# EQTest.net
KiCad netlist of a schematic drawn in EAGLE
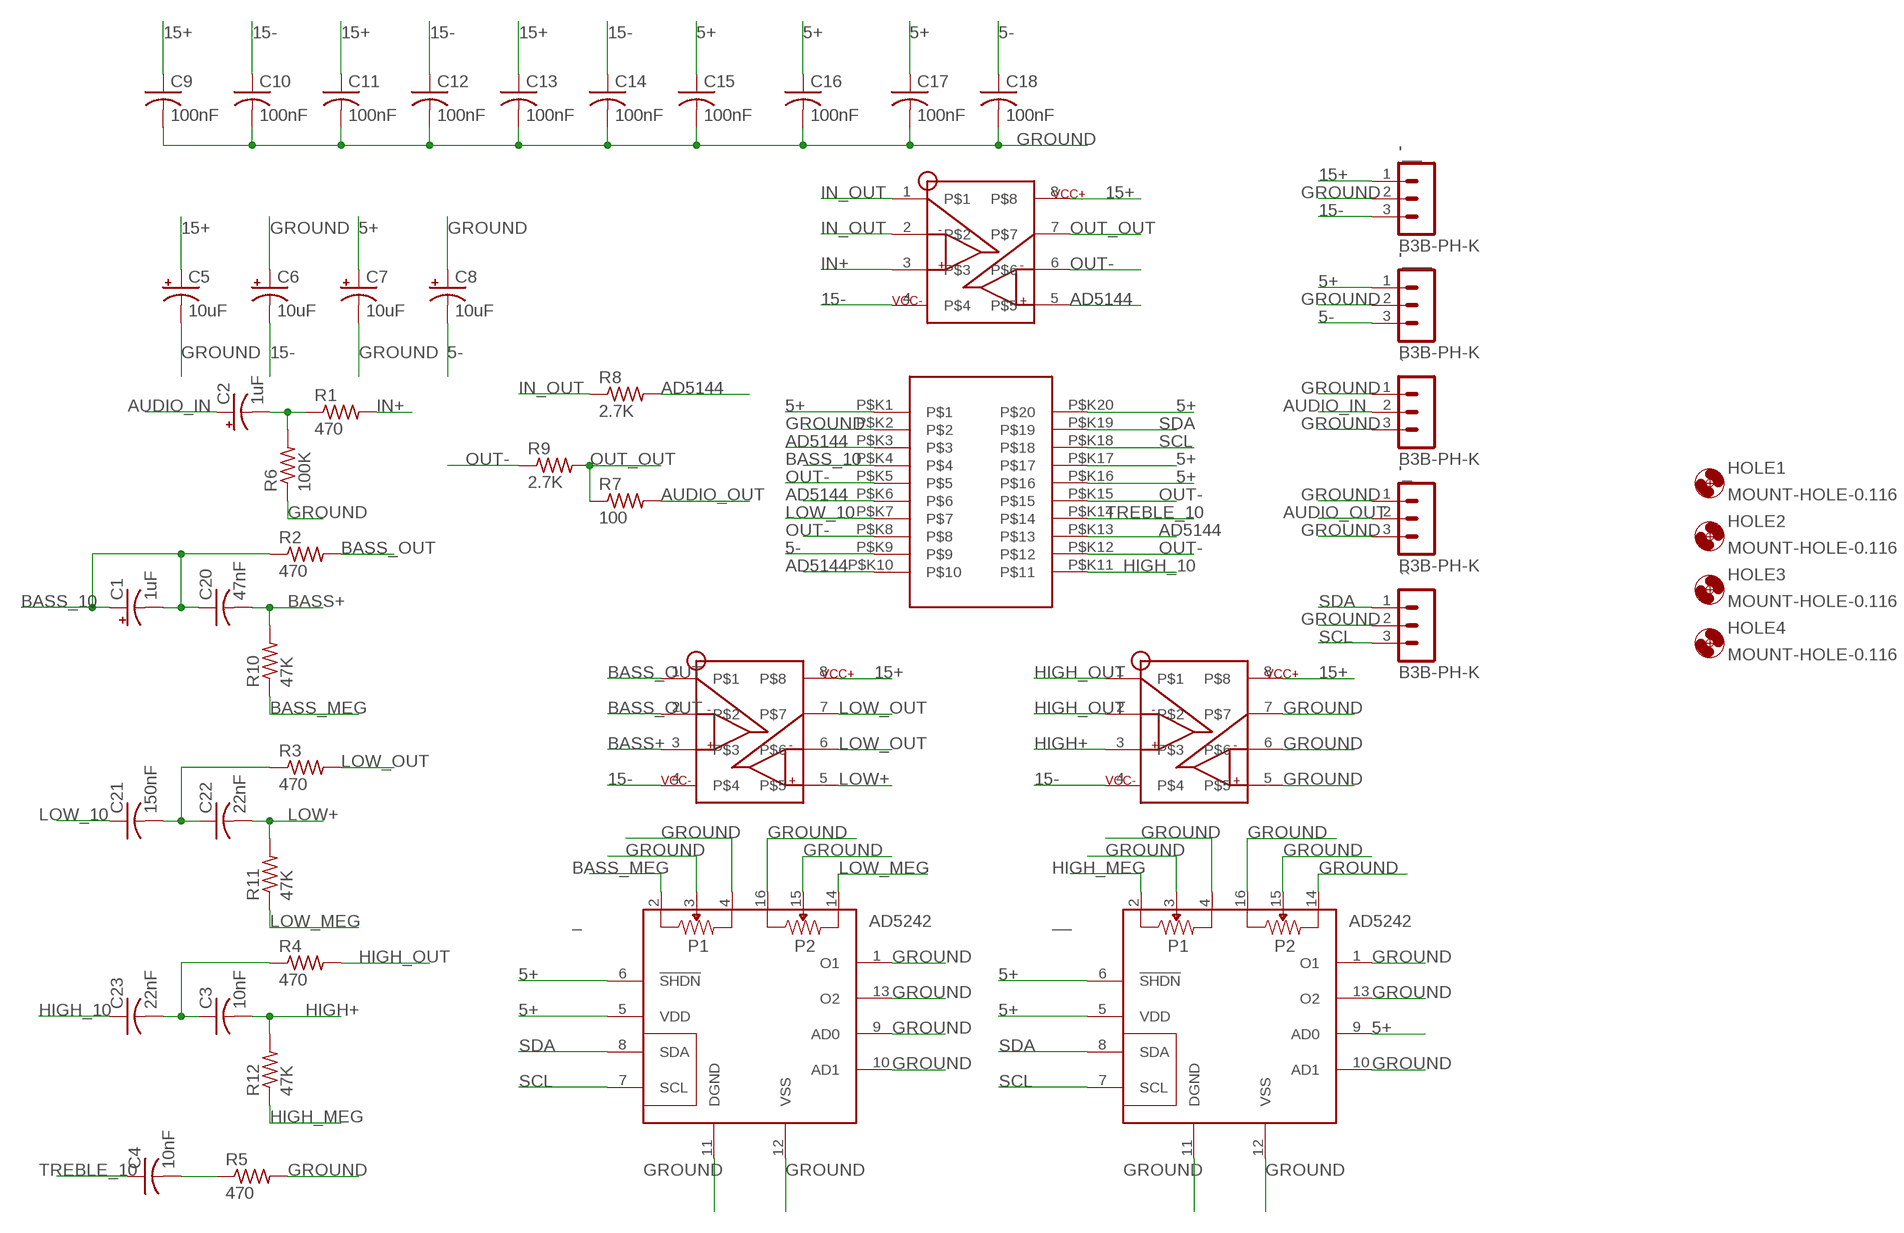
[diagram p0: schematic, sheet 1]

(export (version "E")
  (design (tool "Eeschema 10.0.6"))
  (components
    (comp (ref "'")
      (value "NE5532")
      (footprint "eagle-import:SO08")
      (libsource (lib "eagle-import") (part "NE5532"))
    )
    (comp (ref "''")
      (value "NE5532")
      (footprint "eagle-import:SO08")
      (libsource (lib "eagle-import") (part "NE5532"))
    )
    (comp (ref "'''")
      (value "NE5532")
      (footprint "eagle-import:SO08")
      (libsource (lib "eagle-import") (part "NE5532"))
    )
    (comp (ref "'_")
      (value "B3B-PH-K")
      (footprint "eagle-import:B3B-PH-K")
      (libsource (lib "eagle-import") (part "B3B-PH-K"))
    )
    (comp (ref "'__")
      (value "B3B-PH-K")
      (footprint "eagle-import:B3B-PH-K")
      (libsource (lib "eagle-import") (part "B3B-PH-K"))
    )
    (comp (ref "'___")
      (value "B3B-PH-K")
      (footprint "eagle-import:B3B-PH-K")
      (libsource (lib "eagle-import") (part "B3B-PH-K"))
    )
    (comp (ref "10K")
      (value "TSSOP20")
      (footprint "eagle-import:TSSOP20")
      (libsource (lib "eagle-import") (part "TSSOP20"))
    )
    (comp (ref "C1")
      (value "1uF")
      (footprint "eagle-import:E2-5")
      (libsource (lib "eagle-import") (part "CPOL-USE2-5"))
    )
    (comp (ref "C2")
      (value "1uF")
      (footprint "eagle-import:E2-5")
      (libsource (lib "eagle-import") (part "CPOL-USE2-5"))
    )
    (comp (ref "C3")
      (value "10nF")
      (footprint "eagle-import:C1206K")
      (libsource (lib "eagle-import") (part "C-USC1206K"))
    )
    (comp (ref "C4")
      (value "10nF")
      (footprint "eagle-import:C1206K")
      (libsource (lib "eagle-import") (part "C-USC1206K"))
    )
    (comp (ref "C5")
      (value "10uF")
      (footprint "eagle-import:E3,5-8")
      (libsource (lib "eagle-import") (part "CPOL-USE3.5-8"))
    )
    (comp (ref "C6")
      (value "10uF")
      (footprint "eagle-import:E3,5-8")
      (libsource (lib "eagle-import") (part "CPOL-USE3.5-8"))
    )
    (comp (ref "C7")
      (value "10uF")
      (footprint "eagle-import:E3,5-8")
      (libsource (lib "eagle-import") (part "CPOL-USE3.5-8"))
    )
    (comp (ref "C8")
      (value "10uF")
      (footprint "eagle-import:E3,5-8")
      (libsource (lib "eagle-import") (part "CPOL-USE3.5-8"))
    )
    (comp (ref "C9")
      (value "100nF")
      (footprint "eagle-import:C1206K")
      (libsource (lib "eagle-import") (part "C-USC1206K"))
    )
    (comp (ref "C10")
      (value "100nF")
      (footprint "eagle-import:C1206K")
      (libsource (lib "eagle-import") (part "C-USC1206K"))
    )
    (comp (ref "C11")
      (value "100nF")
      (footprint "eagle-import:C1206K")
      (libsource (lib "eagle-import") (part "C-USC1206K"))
    )
    (comp (ref "C12")
      (value "100nF")
      (footprint "eagle-import:C1206K")
      (libsource (lib "eagle-import") (part "C-USC1206K"))
    )
    (comp (ref "C13")
      (value "100nF")
      (footprint "eagle-import:C1206K")
      (libsource (lib "eagle-import") (part "C-USC1206K"))
    )
    (comp (ref "C14")
      (value "100nF")
      (footprint "eagle-import:C1206K")
      (libsource (lib "eagle-import") (part "C-USC1206K"))
    )
    (comp (ref "C15")
      (value "100nF")
      (footprint "eagle-import:C1206K")
      (libsource (lib "eagle-import") (part "C-USC1206K"))
    )
    (comp (ref "C16")
      (value "100nF")
      (footprint "eagle-import:C1206K")
      (libsource (lib "eagle-import") (part "C-USC1206K"))
    )
    (comp (ref "C17")
      (value "100nF")
      (footprint "eagle-import:C1206K")
      (libsource (lib "eagle-import") (part "C-USC1206K"))
    )
    (comp (ref "C18")
      (value "100nF")
      (footprint "eagle-import:C1206K")
      (libsource (lib "eagle-import") (part "C-USC1206K"))
    )
    (comp (ref "C20")
      (value "47nF")
      (footprint "eagle-import:C1206K")
      (libsource (lib "eagle-import") (part "C-USC1206K"))
    )
    (comp (ref "C21")
      (value "150nF")
      (footprint "eagle-import:C1206K")
      (libsource (lib "eagle-import") (part "C-USC1206K"))
    )
    (comp (ref "C22")
      (value "22nF")
      (footprint "eagle-import:C1206K")
      (libsource (lib "eagle-import") (part "C-USC1206K"))
    )
    (comp (ref "C23")
      (value "22nF")
      (footprint "eagle-import:C1206K")
      (libsource (lib "eagle-import") (part "C-USC1206K"))
    )
    (comp (ref "HOLE1")
      (value "MOUNT-HOLE-0.116")
      (footprint "eagle-import:116")
      (libsource (lib "eagle-import") (part "MOUNT-HOLE-0.116"))
    )
    (comp (ref "HOLE2")
      (value "MOUNT-HOLE-0.116")
      (footprint "eagle-import:116")
      (libsource (lib "eagle-import") (part "MOUNT-HOLE-0.116"))
    )
    (comp (ref "HOLE3")
      (value "MOUNT-HOLE-0.116")
      (footprint "eagle-import:116")
      (libsource (lib "eagle-import") (part "MOUNT-HOLE-0.116"))
    )
    (comp (ref "HOLE4")
      (value "MOUNT-HOLE-0.116")
      (footprint "eagle-import:116")
      (libsource (lib "eagle-import") (part "MOUNT-HOLE-0.116"))
    )
    (comp (ref "R1")
      (value "470")
      (footprint "eagle-import:R1206")
      (libsource (lib "eagle-import") (part "R-US_R1206"))
    )
    (comp (ref "R2")
      (value "470")
      (footprint "eagle-import:R1206")
      (libsource (lib "eagle-import") (part "R-US_R1206"))
    )
    (comp (ref "R3")
      (value "470")
      (footprint "eagle-import:R1206")
      (libsource (lib "eagle-import") (part "R-US_R1206"))
    )
    (comp (ref "R4")
      (value "470")
      (footprint "eagle-import:R1206")
      (libsource (lib "eagle-import") (part "R-US_R1206"))
    )
    (comp (ref "R5")
      (value "470")
      (footprint "eagle-import:R1206")
      (libsource (lib "eagle-import") (part "R-US_R1206"))
    )
    (comp (ref "R6")
      (value "100K")
      (footprint "eagle-import:R1206")
      (libsource (lib "eagle-import") (part "R-US_R1206"))
    )
    (comp (ref "R7")
      (value "100")
      (footprint "eagle-import:R1206")
      (libsource (lib "eagle-import") (part "R-US_R1206"))
    )
    (comp (ref "R8")
      (value "2.7K")
      (footprint "eagle-import:R1206")
      (libsource (lib "eagle-import") (part "R-US_R1206"))
    )
    (comp (ref "R9")
      (value "2.7K")
      (footprint "eagle-import:R1206")
      (libsource (lib "eagle-import") (part "R-US_R1206"))
    )
    (comp (ref "R10")
      (value "47K")
      (footprint "eagle-import:R1206")
      (libsource (lib "eagle-import") (part "R-US_R1206"))
    )
    (comp (ref "R11")
      (value "47K")
      (footprint "eagle-import:R1206")
      (libsource (lib "eagle-import") (part "R-US_R1206"))
    )
    (comp (ref "R12")
      (value "47K")
      (footprint "eagle-import:R1206")
      (libsource (lib "eagle-import") (part "R-US_R1206"))
    )
    (comp (ref "_")
      (value "AD5242")
      (footprint "eagle-import:TSSOP16")
      (libsource (lib "eagle-import") (part "AD5242"))
    )
    (comp (ref "__")
      (value "AD5242")
      (footprint "eagle-import:TSSOP16")
      (libsource (lib "eagle-import") (part "AD5242"))
    )
    (comp (ref "`")
      (value "B3B-PH-K")
      (footprint "eagle-import:B3B-PH-K")
      (libsource (lib "eagle-import") (part "B3B-PH-K"))
    )
    (comp (ref "``")
      (value "B3B-PH-K")
      (footprint "eagle-import:B3B-PH-K")
      (libsource (lib "eagle-import") (part "B3B-PH-K"))
    )
  )
  (nets
    (net (code "1") (name "/5+") (class "Default")
      (node (ref "'___") (pin "1") (pinfunction "1_1") (pintype "passive"))
      (node (ref "10K") (pin "P$K1") (pinfunction "P$1_P$K1") (pintype "bidirectional"))
      (node (ref "10K") (pin "P$K16") (pinfunction "P$16_P$K16") (pintype "bidirectional"))
      (node (ref "10K") (pin "P$K17") (pinfunction "P$17_P$K17") (pintype "bidirectional"))
      (node (ref "10K") (pin "P$K20") (pinfunction "P$20_P$K20") (pintype "bidirectional"))
      (node (ref "C15") (pin "1") (pinfunction "1_1") (pintype "passive"))
      (node (ref "C16") (pin "1") (pinfunction "1_1") (pintype "passive"))
      (node (ref "C17") (pin "1") (pinfunction "1_1") (pintype "passive"))
      (node (ref "C7") (pin "+") (pinfunction "+_+") (pintype "passive"))
      (node (ref "_") (pin "5") (pinfunction "VDD_5") (pintype "bidirectional"))
      (node (ref "_") (pin "6") (pinfunction "~{SHDN}_6") (pintype "bidirectional"))
      (node (ref "__") (pin "5") (pinfunction "VDD_5") (pintype "bidirectional"))
      (node (ref "__") (pin "6") (pinfunction "~{SHDN}_6") (pintype "bidirectional"))
      (node (ref "__") (pin "9") (pinfunction "AD0_9") (pintype "bidirectional"))
    )
    (net (code "2") (name "/5-") (class "Default")
      (node (ref "'___") (pin "3") (pinfunction "3_3") (pintype "passive"))
      (node (ref "10K") (pin "P$K9") (pinfunction "P$9_P$K9") (pintype "bidirectional"))
      (node (ref "C18") (pin "1") (pinfunction "1_1") (pintype "passive"))
      (node (ref "C8") (pin "-") (pinfunction "-_-") (pintype "passive"))
    )
    (net (code "3") (name "/15+") (class "Default")
      (node (ref "'") (pin "8") (pinfunction "P$8_8") (pintype "bidirectional"))
      (node (ref "''") (pin "8") (pinfunction "P$8_8") (pintype "bidirectional"))
      (node (ref "'''") (pin "8") (pinfunction "P$8_8") (pintype "bidirectional"))
      (node (ref "'__") (pin "1") (pinfunction "1_1") (pintype "passive"))
      (node (ref "C11") (pin "1") (pinfunction "1_1") (pintype "passive"))
      (node (ref "C13") (pin "1") (pinfunction "1_1") (pintype "passive"))
      (node (ref "C5") (pin "+") (pinfunction "+_+") (pintype "passive"))
      (node (ref "C9") (pin "1") (pinfunction "1_1") (pintype "passive"))
    )
    (net (code "4") (name "/15-") (class "Default")
      (node (ref "'") (pin "4") (pinfunction "P$4_4") (pintype "bidirectional"))
      (node (ref "''") (pin "4") (pinfunction "P$4_4") (pintype "bidirectional"))
      (node (ref "'''") (pin "4") (pinfunction "P$4_4") (pintype "bidirectional"))
      (node (ref "'__") (pin "3") (pinfunction "3_3") (pintype "passive"))
      (node (ref "C10") (pin "1") (pinfunction "1_1") (pintype "passive"))
      (node (ref "C12") (pin "1") (pinfunction "1_1") (pintype "passive"))
      (node (ref "C14") (pin "1") (pinfunction "1_1") (pintype "passive"))
      (node (ref "C6") (pin "-") (pinfunction "-_-") (pintype "passive"))
    )
    (net (code "5") (name "/AD5144") (class "Default")
      (node (ref "'") (pin "5") (pinfunction "P$5_5") (pintype "bidirectional"))
      (node (ref "10K") (pin "P$K10") (pinfunction "P$10_P$K10") (pintype "bidirectional"))
      (node (ref "10K") (pin "P$K13") (pinfunction "P$13_P$K13") (pintype "bidirectional"))
      (node (ref "10K") (pin "P$K3") (pinfunction "P$3_P$K3") (pintype "bidirectional"))
      (node (ref "10K") (pin "P$K6") (pinfunction "P$6_P$K6") (pintype "bidirectional"))
      (node (ref "R8") (pin "2") (pinfunction "2_2") (pintype "passive"))
    )
    (net (code "6") (name "/AUDIO_IN") (class "Default")
      (node (ref "C2") (pin "+") (pinfunction "+_+") (pintype "passive"))
      (node (ref "`") (pin "2") (pinfunction "2_2") (pintype "passive"))
    )
    (net (code "7") (name "/AUDIO_OUT") (class "Default")
      (node (ref "'_") (pin "2") (pinfunction "2_2") (pintype "passive"))
      (node (ref "R7") (pin "2") (pinfunction "2_2") (pintype "passive"))
    )
    (net (code "8") (name "/BASS+") (class "Default")
      (node (ref "''") (pin "3") (pinfunction "P$3_3") (pintype "bidirectional"))
      (node (ref "C20") (pin "2") (pinfunction "2_2") (pintype "passive"))
      (node (ref "R10") (pin "2") (pinfunction "2_2") (pintype "passive"))
    )
    (net (code "9") (name "/BASS_10") (class "Default")
      (node (ref "10K") (pin "P$K4") (pinfunction "P$4_P$K4") (pintype "bidirectional"))
      (node (ref "C1") (pin "+") (pinfunction "+_+") (pintype "passive"))
      (node (ref "C1") (pin "-") (pinfunction "-_-") (pintype "passive"))
      (node (ref "C20") (pin "1") (pinfunction "1_1") (pintype "passive"))
      (node (ref "R2") (pin "1") (pinfunction "1_1") (pintype "passive"))
    )
    (net (code "10") (name "/BASS_MEG") (class "Default")
      (node (ref "R10") (pin "1") (pinfunction "1_1") (pintype "passive"))
      (node (ref "_") (pin "2") (pinfunction "A1_2") (pintype "bidirectional"))
    )
    (net (code "11") (name "/BASS_OUT") (class "Default")
      (node (ref "''") (pin "1") (pinfunction "P$1_1") (pintype "bidirectional"))
      (node (ref "''") (pin "2") (pinfunction "P$2_2") (pintype "bidirectional"))
      (node (ref "R2") (pin "2") (pinfunction "2_2") (pintype "passive"))
    )
    (net (code "12") (name "/GROUND") (class "Default")
      (node (ref "'''") (pin "5") (pinfunction "P$5_5") (pintype "bidirectional"))
      (node (ref "'''") (pin "6") (pinfunction "P$6_6") (pintype "bidirectional"))
      (node (ref "'''") (pin "7") (pinfunction "P$7_7") (pintype "bidirectional"))
      (node (ref "'_") (pin "1") (pinfunction "1_1") (pintype "passive"))
      (node (ref "'_") (pin "3") (pinfunction "3_3") (pintype "passive"))
      (node (ref "'__") (pin "2") (pinfunction "2_2") (pintype "passive"))
      (node (ref "'___") (pin "2") (pinfunction "2_2") (pintype "passive"))
      (node (ref "10K") (pin "P$K2") (pinfunction "P$2_P$K2") (pintype "bidirectional"))
      (node (ref "C10") (pin "2") (pinfunction "2_2") (pintype "passive"))
      (node (ref "C11") (pin "2") (pinfunction "2_2") (pintype "passive"))
      (node (ref "C12") (pin "2") (pinfunction "2_2") (pintype "passive"))
      (node (ref "C13") (pin "2") (pinfunction "2_2") (pintype "passive"))
      (node (ref "C14") (pin "2") (pinfunction "2_2") (pintype "passive"))
      (node (ref "C15") (pin "2") (pinfunction "2_2") (pintype "passive"))
      (node (ref "C16") (pin "2") (pinfunction "2_2") (pintype "passive"))
      (node (ref "C17") (pin "2") (pinfunction "2_2") (pintype "passive"))
      (node (ref "C18") (pin "2") (pinfunction "2_2") (pintype "passive"))
      (node (ref "C5") (pin "-") (pinfunction "-_-") (pintype "passive"))
      (node (ref "C6") (pin "+") (pinfunction "+_+") (pintype "passive"))
      (node (ref "C7") (pin "-") (pinfunction "-_-") (pintype "passive"))
      (node (ref "C8") (pin "+") (pinfunction "+_+") (pintype "passive"))
      (node (ref "C9") (pin "2") (pinfunction "2_2") (pintype "passive"))
      (node (ref "R5") (pin "2") (pinfunction "2_2") (pintype "passive"))
      (node (ref "R6") (pin "1") (pinfunction "1_1") (pintype "passive"))
      (node (ref "_") (pin "1") (pinfunction "O1_1") (pintype "bidirectional"))
      (node (ref "_") (pin "10") (pinfunction "AD1_10") (pintype "bidirectional"))
      (node (ref "_") (pin "11") (pinfunction "DGND_11") (pintype "bidirectional"))
      (node (ref "_") (pin "12") (pinfunction "VSS_12") (pintype "bidirectional"))
      (node (ref "_") (pin "13") (pinfunction "O2_13") (pintype "bidirectional"))
      (node (ref "_") (pin "15") (pinfunction "W2_15") (pintype "bidirectional"))
      (node (ref "_") (pin "16") (pinfunction "A2_16") (pintype "bidirectional"))
      (node (ref "_") (pin "3") (pinfunction "W1_3") (pintype "bidirectional"))
      (node (ref "_") (pin "4") (pinfunction "B1_4") (pintype "bidirectional"))
      (node (ref "_") (pin "9") (pinfunction "AD0_9") (pintype "bidirectional"))
      (node (ref "__") (pin "1") (pinfunction "O1_1") (pintype "bidirectional"))
      (node (ref "__") (pin "10") (pinfunction "AD1_10") (pintype "bidirectional"))
      (node (ref "__") (pin "11") (pinfunction "DGND_11") (pintype "bidirectional"))
      (node (ref "__") (pin "12") (pinfunction "VSS_12") (pintype "bidirectional"))
      (node (ref "__") (pin "13") (pinfunction "O2_13") (pintype "bidirectional"))
      (node (ref "__") (pin "14") (pinfunction "B2_14") (pintype "bidirectional"))
      (node (ref "__") (pin "15") (pinfunction "W2_15") (pintype "bidirectional"))
      (node (ref "__") (pin "16") (pinfunction "A2_16") (pintype "bidirectional"))
      (node (ref "__") (pin "3") (pinfunction "W1_3") (pintype "bidirectional"))
      (node (ref "__") (pin "4") (pinfunction "B1_4") (pintype "bidirectional"))
      (node (ref "`") (pin "1") (pinfunction "1_1") (pintype "passive"))
      (node (ref "`") (pin "3") (pinfunction "3_3") (pintype "passive"))
      (node (ref "``") (pin "2") (pinfunction "2_2") (pintype "passive"))
    )
    (net (code "13") (name "/HIGH+") (class "Default")
      (node (ref "'''") (pin "3") (pinfunction "P$3_3") (pintype "bidirectional"))
      (node (ref "C3") (pin "2") (pinfunction "2_2") (pintype "passive"))
      (node (ref "R12") (pin "2") (pinfunction "2_2") (pintype "passive"))
    )
    (net (code "14") (name "/HIGH_10") (class "Default")
      (node (ref "10K") (pin "P$K11") (pinfunction "P$11_P$K11") (pintype "bidirectional"))
      (node (ref "C23") (pin "1") (pinfunction "1_1") (pintype "passive"))
    )
    (net (code "15") (name "/HIGH_MEG") (class "Default")
      (node (ref "R12") (pin "1") (pinfunction "1_1") (pintype "passive"))
      (node (ref "__") (pin "2") (pinfunction "A1_2") (pintype "bidirectional"))
    )
    (net (code "16") (name "/HIGH_OUT") (class "Default")
      (node (ref "'''") (pin "1") (pinfunction "P$1_1") (pintype "bidirectional"))
      (node (ref "'''") (pin "2") (pinfunction "P$2_2") (pintype "bidirectional"))
      (node (ref "R4") (pin "2") (pinfunction "2_2") (pintype "passive"))
    )
    (net (code "17") (name "/IN+") (class "Default")
      (node (ref "'") (pin "3") (pinfunction "P$3_3") (pintype "bidirectional"))
      (node (ref "R1") (pin "2") (pinfunction "2_2") (pintype "passive"))
    )
    (net (code "18") (name "/IN_OUT") (class "Default")
      (node (ref "'") (pin "1") (pinfunction "P$1_1") (pintype "bidirectional"))
      (node (ref "'") (pin "2") (pinfunction "P$2_2") (pintype "bidirectional"))
      (node (ref "R8") (pin "1") (pinfunction "1_1") (pintype "passive"))
    )
    (net (code "19") (name "/LOW+") (class "Default")
      (node (ref "''") (pin "5") (pinfunction "P$5_5") (pintype "bidirectional"))
      (node (ref "C22") (pin "2") (pinfunction "2_2") (pintype "passive"))
      (node (ref "R11") (pin "2") (pinfunction "2_2") (pintype "passive"))
    )
    (net (code "20") (name "/LOW_10") (class "Default")
      (node (ref "10K") (pin "P$K7") (pinfunction "P$7_P$K7") (pintype "bidirectional"))
      (node (ref "C21") (pin "1") (pinfunction "1_1") (pintype "passive"))
    )
    (net (code "21") (name "/LOW_MEG") (class "Default")
      (node (ref "R11") (pin "1") (pinfunction "1_1") (pintype "passive"))
      (node (ref "_") (pin "14") (pinfunction "B2_14") (pintype "bidirectional"))
    )
    (net (code "22") (name "/LOW_OUT") (class "Default")
      (node (ref "''") (pin "6") (pinfunction "P$6_6") (pintype "bidirectional"))
      (node (ref "''") (pin "7") (pinfunction "P$7_7") (pintype "bidirectional"))
      (node (ref "R3") (pin "2") (pinfunction "2_2") (pintype "passive"))
    )
    (net (code "23") (name "/OUT-") (class "Default")
      (node (ref "'") (pin "6") (pinfunction "P$6_6") (pintype "bidirectional"))
      (node (ref "10K") (pin "P$K12") (pinfunction "P$12_P$K12") (pintype "bidirectional"))
      (node (ref "10K") (pin "P$K15") (pinfunction "P$15_P$K15") (pintype "bidirectional"))
      (node (ref "10K") (pin "P$K5") (pinfunction "P$5_P$K5") (pintype "bidirectional"))
      (node (ref "10K") (pin "P$K8") (pinfunction "P$8_P$K8") (pintype "bidirectional"))
      (node (ref "R9") (pin "1") (pinfunction "1_1") (pintype "passive"))
    )
    (net (code "24") (name "/OUT_OUT") (class "Default")
      (node (ref "'") (pin "7") (pinfunction "P$7_7") (pintype "bidirectional"))
      (node (ref "R7") (pin "1") (pinfunction "1_1") (pintype "passive"))
      (node (ref "R9") (pin "2") (pinfunction "2_2") (pintype "passive"))
    )
    (net (code "25") (name "/SCL") (class "Default")
      (node (ref "10K") (pin "P$K18") (pinfunction "P$18_P$K18") (pintype "bidirectional"))
      (node (ref "_") (pin "7") (pinfunction "SCL_7") (pintype "bidirectional"))
      (node (ref "__") (pin "7") (pinfunction "SCL_7") (pintype "bidirectional"))
      (node (ref "``") (pin "3") (pinfunction "3_3") (pintype "passive"))
    )
    (net (code "26") (name "/SDA") (class "Default")
      (node (ref "10K") (pin "P$K19") (pinfunction "P$19_P$K19") (pintype "bidirectional"))
      (node (ref "_") (pin "8") (pinfunction "SDA_8") (pintype "bidirectional"))
      (node (ref "__") (pin "8") (pinfunction "SDA_8") (pintype "bidirectional"))
      (node (ref "``") (pin "1") (pinfunction "1_1") (pintype "passive"))
    )
    (net (code "27") (name "/TREBLE_10") (class "Default")
      (node (ref "10K") (pin "P$K14") (pinfunction "P$14_P$K14") (pintype "bidirectional"))
      (node (ref "C4") (pin "1") (pinfunction "1_1") (pintype "passive"))
    )
    (net (code "28") (name "Net-(C2-Pad-)") (class "Default")
      (node (ref "C2") (pin "-") (pinfunction "-_-") (pintype "passive"))
      (node (ref "R1") (pin "1") (pinfunction "1_1") (pintype "passive"))
      (node (ref "R6") (pin "2") (pinfunction "2_2") (pintype "passive"))
    )
    (net (code "29") (name "Net-(C4-Pad2)") (class "Default")
      (node (ref "C4") (pin "2") (pinfunction "2_2") (pintype "passive"))
      (node (ref "R5") (pin "1") (pinfunction "1_1") (pintype "passive"))
    )
    (net (code "30") (name "Net-(C21-Pad2)") (class "Default")
      (node (ref "C21") (pin "2") (pinfunction "2_2") (pintype "passive"))
      (node (ref "C22") (pin "1") (pinfunction "1_1") (pintype "passive"))
      (node (ref "R3") (pin "1") (pinfunction "1_1") (pintype "passive"))
    )
    (net (code "31") (name "Net-(C23-Pad2)") (class "Default")
      (node (ref "C23") (pin "2") (pinfunction "2_2") (pintype "passive"))
      (node (ref "C3") (pin "1") (pinfunction "1_1") (pintype "passive"))
      (node (ref "R4") (pin "1") (pinfunction "1_1") (pintype "passive"))
    )
  )
)
